# 05_IO_CONN.net
KiCad netlist of a schematic drawn in Altium Designer
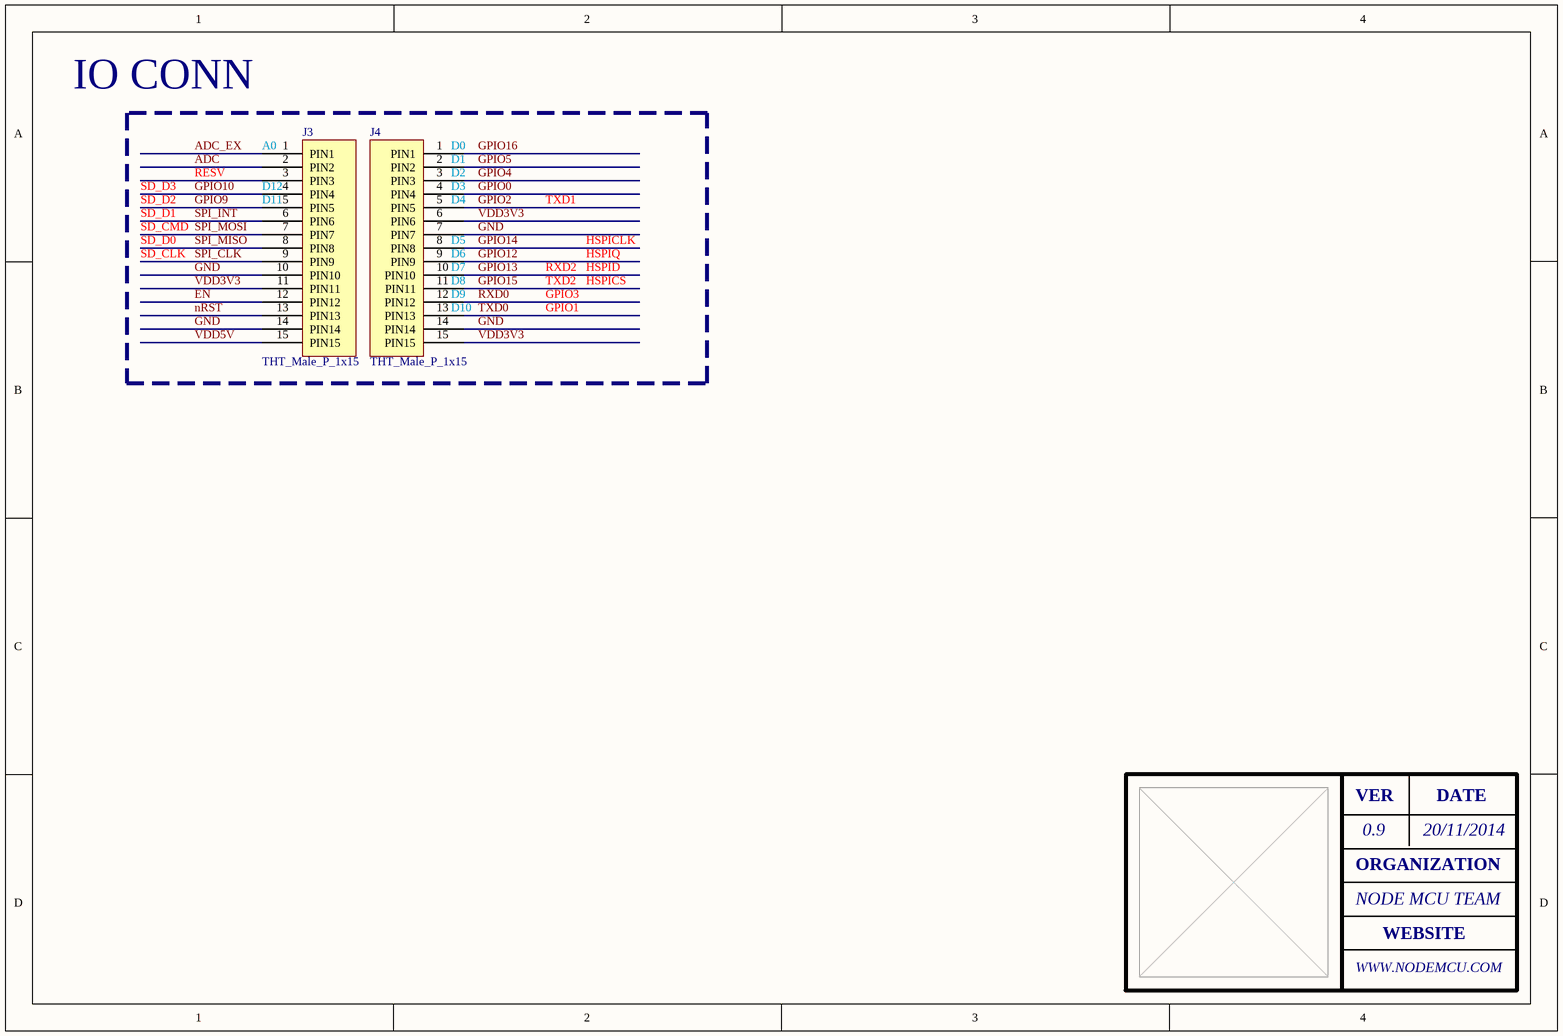
[diagram p0: 05_IO_CONN.SchDoc]

(export (version "E")
  (design (tool "Eeschema 10.0.6"))
  (components
    (comp (ref "J3")
      (value "THT_Male_P_1x15")
      (footprint "THT_Male_P_1x15-2.54mm")
      (description "THT Male pin header strip 1x15")
      (libsource (lib "") (part "THT_Male_P_1x15_1"))
    )
    (comp (ref "J4")
      (value "THT_Male_P_1x15")
      (footprint "THT_Male_P_1x15-2.54mm")
      (description "THT Male pin header strip 1x15")
      (libsource (lib "Vowstar_Connector") (part "THT_Male_P_1x15"))
    )
  )
  (nets
    (net (code "1") (name "/ADC") (class "Default")
      (node (ref "J3") (pin "2") (pinfunction "PIN2_2") (pintype "passive"))
    )
    (net (code "2") (name "/ADC_EX") (class "Default")
      (node (ref "J3") (pin "1") (pinfunction "PIN1_1") (pintype "passive"))
    )
    (net (code "3") (name "/EN") (class "Default")
      (node (ref "J3") (pin "12") (pinfunction "PIN12_12") (pintype "passive"))
    )
    (net (code "4") (name "/GND") (class "Default")
      (node (ref "J3") (pin "10") (pinfunction "PIN10_10") (pintype "passive"))
      (node (ref "J3") (pin "14") (pinfunction "PIN14_14") (pintype "passive"))
      (node (ref "J4") (pin "14") (pinfunction "PIN14_14") (pintype "passive"))
      (node (ref "J4") (pin "7") (pinfunction "PIN7_7") (pintype "passive"))
    )
    (net (code "5") (name "/GPIO0") (class "Default")
      (node (ref "J4") (pin "4") (pinfunction "PIN4_4") (pintype "passive"))
    )
    (net (code "6") (name "/GPIO2") (class "Default")
      (node (ref "J4") (pin "5") (pinfunction "PIN5_5") (pintype "passive"))
    )
    (net (code "7") (name "/GPIO4") (class "Default")
      (node (ref "J4") (pin "3") (pinfunction "PIN3_3") (pintype "passive"))
    )
    (net (code "8") (name "/GPIO5") (class "Default")
      (node (ref "J4") (pin "2") (pinfunction "PIN2_2") (pintype "passive"))
    )
    (net (code "9") (name "/GPIO9") (class "Default")
      (node (ref "J3") (pin "5") (pinfunction "PIN5_5") (pintype "passive"))
    )
    (net (code "10") (name "/GPIO10") (class "Default")
      (node (ref "J3") (pin "4") (pinfunction "PIN4_4") (pintype "passive"))
    )
    (net (code "11") (name "/GPIO12") (class "Default")
      (node (ref "J4") (pin "9") (pinfunction "PIN9_9") (pintype "passive"))
    )
    (net (code "12") (name "/GPIO13") (class "Default")
      (node (ref "J4") (pin "10") (pinfunction "PIN10_10") (pintype "passive"))
    )
    (net (code "13") (name "/GPIO14") (class "Default")
      (node (ref "J4") (pin "8") (pinfunction "PIN8_8") (pintype "passive"))
    )
    (net (code "14") (name "/GPIO15") (class "Default")
      (node (ref "J4") (pin "11") (pinfunction "PIN11_11") (pintype "passive"))
    )
    (net (code "15") (name "/GPIO16") (class "Default")
      (node (ref "J4") (pin "1") (pinfunction "PIN1_1") (pintype "passive"))
    )
    (net (code "16") (name "/RXD0") (class "Default")
      (node (ref "J4") (pin "12") (pinfunction "PIN12_12") (pintype "passive"))
    )
    (net (code "17") (name "/SPI_CLK") (class "Default")
      (node (ref "J3") (pin "9") (pinfunction "PIN9_9") (pintype "passive"))
    )
    (net (code "18") (name "/SPI_INT") (class "Default")
      (node (ref "J3") (pin "6") (pinfunction "PIN6_6") (pintype "passive"))
    )
    (net (code "19") (name "/SPI_MISO") (class "Default")
      (node (ref "J3") (pin "8") (pinfunction "PIN8_8") (pintype "passive"))
    )
    (net (code "20") (name "/SPI_MOSI") (class "Default")
      (node (ref "J3") (pin "7") (pinfunction "PIN7_7") (pintype "passive"))
    )
    (net (code "21") (name "/TXD0") (class "Default")
      (node (ref "J4") (pin "13") (pinfunction "PIN13_13") (pintype "passive"))
    )
    (net (code "22") (name "/VDD3V3") (class "Default")
      (node (ref "J3") (pin "11") (pinfunction "PIN11_11") (pintype "passive"))
      (node (ref "J4") (pin "15") (pinfunction "PIN15_15") (pintype "passive"))
      (node (ref "J4") (pin "6") (pinfunction "PIN6_6") (pintype "passive"))
    )
    (net (code "23") (name "/VDD5V") (class "Default")
      (node (ref "J3") (pin "15") (pinfunction "PIN15_15") (pintype "passive"))
    )
    (net (code "24") (name "/nRST") (class "Default")
      (node (ref "J3") (pin "13") (pinfunction "PIN13_13") (pintype "passive"))
    )
    (net (code "25") (name "unconnected-(J3-PIN3-Pad3)") (class "Default")
      (node (ref "J3") (pin "3") (pinfunction "PIN3_3") (pintype "passive"))
    )
  )
)
